# Sch_energia_luces.net
KiCad netlist of a schematic drawn in Altium Designer
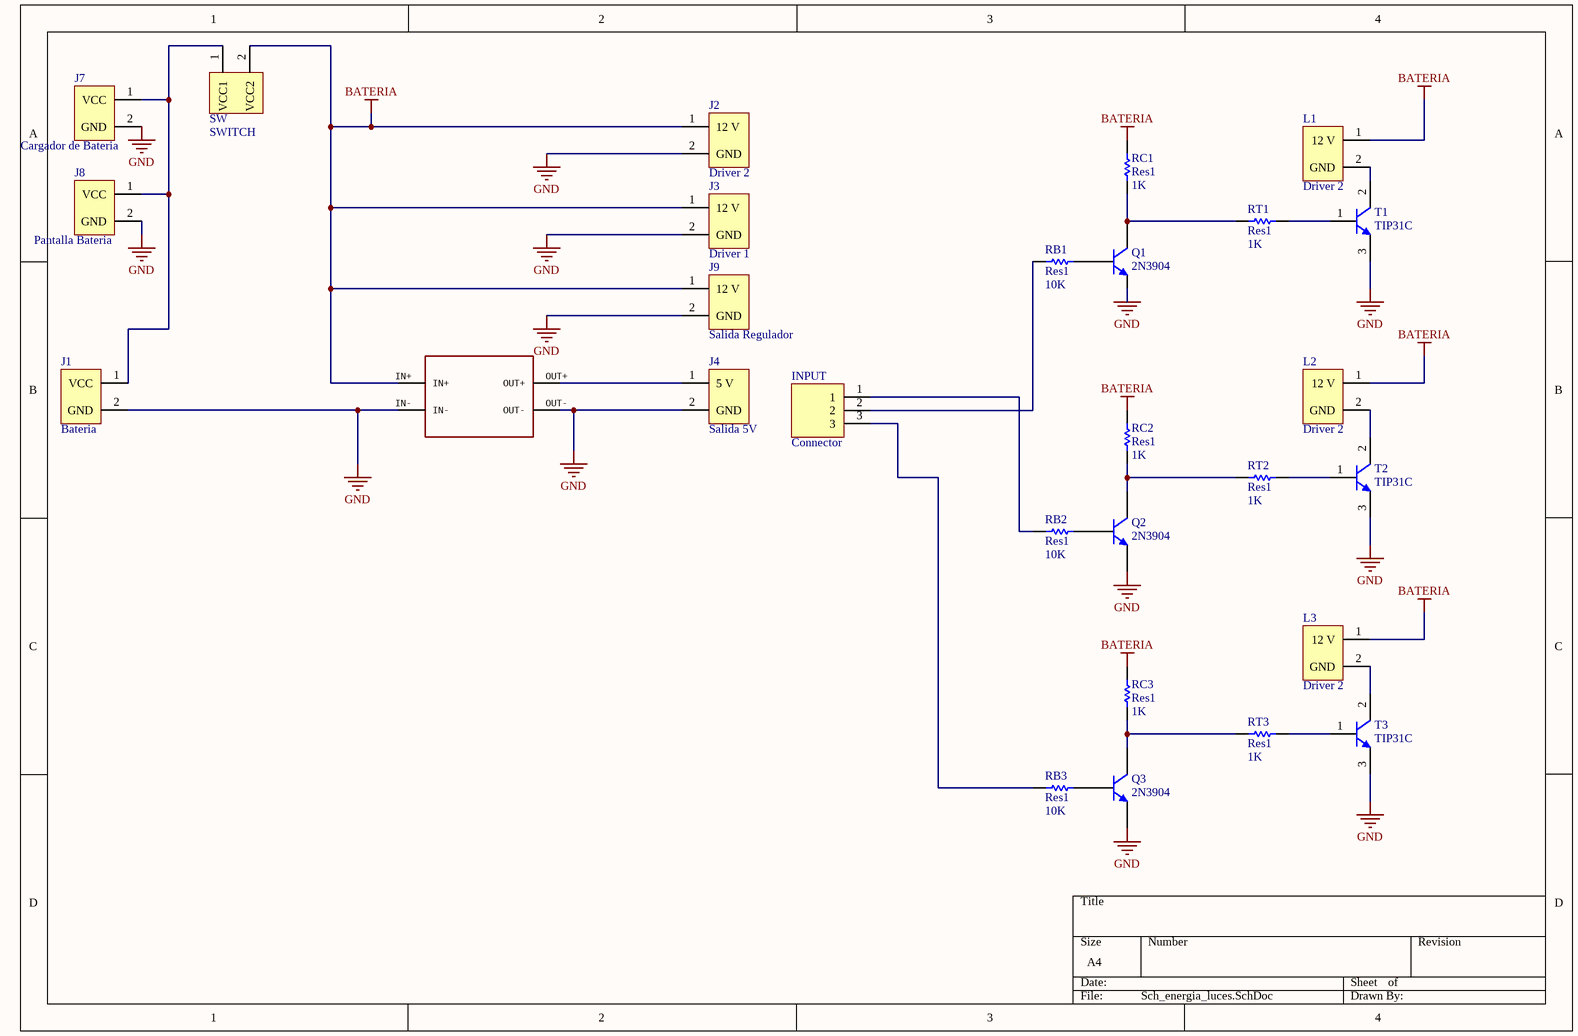
[diagram p0: Sch_energia_luces.SchDoc]

(export (version "E")
  (design (tool "Eeschema 10.0.6"))
  (components
    (comp (ref "INPUT")
      (value "Connector")
      (footprint "1x3x2.54 Pin Header TH V")
      (libsource (lib "CARO") (part "Header 1x3"))
    )
    (comp (ref "J1") (value "Bateria") (footprint "CONN2") (libsource (lib "Schlib1") (part "Bornera")))
    (comp (ref "J2") (value "Driver 2") (footprint "CONN2") (libsource (lib "") (part "Bornera_1")))
    (comp (ref "J3") (value "Driver 1") (footprint "CONN2") (libsource (lib "") (part "Bornera_1")))
    (comp (ref "J4") (value "Salida 5V") (footprint "CONN2") (libsource (lib "") (part "Bornera_2")))
    (comp (ref "J7")
      (value "Cargador de Bateria")
      (footprint "CONN2")
      (libsource (lib "Schlib1") (part "Bornera"))
    )
    (comp (ref "J8")
      (value "Pantalla Bateria")
      (footprint "CONN2")
      (libsource (lib "Schlib1") (part "Bornera"))
    )
    (comp (ref "J9") (value "Salida Regulador") (footprint "CONN2") (libsource (lib "") (part "Bornera_1")))
    (comp (ref "L1") (value "Driver 2") (footprint "CONN2") (libsource (lib "Schlib1") (part "Bornera")))
    (comp (ref "L2") (value "Driver 2") (footprint "CONN2") (libsource (lib "Schlib1") (part "Bornera")))
    (comp (ref "L3") (value "Driver 2") (footprint "CONN2") (libsource (lib "Schlib1") (part "Bornera")))
    (comp (ref "Q1")
      (value "2N3904")
      (footprint "TO-92A")
      (description "NPN General Purpose Amplifier")
      (fields (field (name "PUBLISHER") "Altium Limited"))
      (libsource (lib "Miscellaneous Devices") (part "2N3904"))
    )
    (comp (ref "Q2")
      (value "2N3904")
      (footprint "TO-92A")
      (description "NPN General Purpose Amplifier")
      (fields (field (name "PUBLISHER") "Altium Limited"))
      (libsource (lib "Miscellaneous Devices") (part "2N3904"))
    )
    (comp (ref "Q3")
      (value "2N3904")
      (footprint "TO-92A")
      (description "NPN General Purpose Amplifier")
      (fields (field (name "PUBLISHER") "Altium Limited"))
      (libsource (lib "Miscellaneous Devices") (part "2N3904"))
    )
    (comp (ref "RB1")
      (value "Res1")
      (footprint "AXIAL-0.3")
      (description "Resistor")
      (fields (field (name "ALTIUM_VALUE") "10K") (field (name "PUBLISHER") "Altium Limited"))
      (libsource (lib "Miscellaneous Devices") (part "Res1"))
    )
    (comp (ref "RB2")
      (value "Res1")
      (footprint "AXIAL-0.3")
      (description "Resistor")
      (fields (field (name "ALTIUM_VALUE") "10K") (field (name "PUBLISHER") "Altium Limited"))
      (libsource (lib "Miscellaneous Devices") (part "Res1"))
    )
    (comp (ref "RB3")
      (value "Res1")
      (footprint "AXIAL-0.3")
      (description "Resistor")
      (fields (field (name "ALTIUM_VALUE") "10K") (field (name "PUBLISHER") "Altium Limited"))
      (libsource (lib "Miscellaneous Devices") (part "Res1"))
    )
    (comp (ref "RC1")
      (value "Res1")
      (footprint "AXIAL-0.3")
      (description "Resistor")
      (fields (field (name "ALTIUM_VALUE") "1K") (field (name "PUBLISHER") "Altium Limited"))
      (libsource (lib "Miscellaneous Devices") (part "Res1"))
    )
    (comp (ref "RC2")
      (value "Res1")
      (footprint "AXIAL-0.3")
      (description "Resistor")
      (fields (field (name "ALTIUM_VALUE") "1K") (field (name "PUBLISHER") "Altium Limited"))
      (libsource (lib "Miscellaneous Devices") (part "Res1"))
    )
    (comp (ref "RC3")
      (value "Res1")
      (footprint "AXIAL-0.3")
      (description "Resistor")
      (fields (field (name "ALTIUM_VALUE") "1K") (field (name "PUBLISHER") "Altium Limited"))
      (libsource (lib "Miscellaneous Devices") (part "Res1"))
    )
    (comp (ref "REG1")
      (value "Voltage regulator IN: 7-35V OUT: ADJ")
      (footprint "CP8-ADJ")
      (fields (field (name "LIBRARYNAME") "userlib"))
      (libsource (lib "Integrated_Library1") (part "CP8-ADJ"))
    )
    (comp (ref "RT1")
      (value "Res1")
      (footprint "AXIAL-0.3")
      (description "Resistor")
      (fields (field (name "ALTIUM_VALUE") "1K") (field (name "PUBLISHER") "Altium Limited"))
      (libsource (lib "Miscellaneous Devices") (part "Res1"))
    )
    (comp (ref "RT2")
      (value "Res1")
      (footprint "AXIAL-0.3")
      (description "Resistor")
      (fields (field (name "ALTIUM_VALUE") "1K") (field (name "PUBLISHER") "Altium Limited"))
      (libsource (lib "Miscellaneous Devices") (part "Res1"))
    )
    (comp (ref "RT3")
      (value "Res1")
      (footprint "AXIAL-0.3")
      (description "Resistor")
      (fields (field (name "ALTIUM_VALUE") "1K") (field (name "PUBLISHER") "Altium Limited"))
      (libsource (lib "Miscellaneous Devices") (part "Res1"))
    )
    (comp (ref "SW") (value "SWITCH") (footprint "CONN2") (libsource (lib "") (part "Bornera_3")))
    (comp (ref "T1")
      (value "TIP31C")
      (footprint "ONSC-TO-220-3-221A-09")
      (description "Complementary Silicon Plastic Power Transistor, 3-Pin TO-220, Tube")
      (fields (field (name "MANUFACTURER") "On Semiconductor"))
      (libsource (lib "Altium Content Vault") (part "ONSC-NPN-B1C2E3-3_C"))
    )
    (comp (ref "T2")
      (value "TIP31C")
      (footprint "ONSC-TO-220-3-221A-09")
      (description "Complementary Silicon Plastic Power Transistor, 3-Pin TO-220, Tube")
      (fields (field (name "MANUFACTURER") "On Semiconductor"))
      (libsource (lib "Altium Content Vault") (part "ONSC-NPN-B1C2E3-3_C"))
    )
    (comp (ref "T3")
      (value "TIP31C")
      (footprint "ONSC-TO-220-3-221A-09")
      (description "Complementary Silicon Plastic Power Transistor, 3-Pin TO-220, Tube")
      (fields (field (name "MANUFACTURER") "On Semiconductor"))
      (libsource (lib "Altium Content Vault") (part "ONSC-NPN-B1C2E3-3_C"))
    )
  )
  (nets
    (net (code "1") (name "BATERIA") (class "Default")
      (node (ref "J2") (pin "1") (pinfunction "12_V_1") (pintype "passive"))
      (node (ref "J3") (pin "1") (pinfunction "12_V_1") (pintype "passive"))
      (node (ref "J9") (pin "1") (pinfunction "12_V_1") (pintype "passive"))
      (node (ref "L1") (pin "1") (pinfunction "VCC_1") (pintype "passive"))
      (node (ref "L2") (pin "1") (pinfunction "VCC_1") (pintype "passive"))
      (node (ref "L3") (pin "1") (pinfunction "VCC_1") (pintype "passive"))
      (node (ref "RC1") (pin "2") (pinfunction "2_2") (pintype "passive"))
      (node (ref "RC2") (pin "2") (pinfunction "2_2") (pintype "passive"))
      (node (ref "RC3") (pin "2") (pinfunction "2_2") (pintype "passive"))
      (node (ref "REG1") (pin "IN+") (pinfunction "IN+_IN+") (pintype "passive"))
      (node (ref "SW") (pin "2") (pinfunction "VCC2_2") (pintype "passive"))
    )
    (net (code "2") (name "GND") (class "Default")
      (node (ref "J1") (pin "2") (pinfunction "GND_2") (pintype "passive"))
      (node (ref "J2") (pin "2") (pinfunction "GND_2") (pintype "passive"))
      (node (ref "J3") (pin "2") (pinfunction "GND_2") (pintype "passive"))
      (node (ref "J4") (pin "2") (pinfunction "GND_2") (pintype "passive"))
      (node (ref "J7") (pin "2") (pinfunction "GND_2") (pintype "passive"))
      (node (ref "J8") (pin "2") (pinfunction "GND_2") (pintype "passive"))
      (node (ref "J9") (pin "2") (pinfunction "GND_2") (pintype "passive"))
      (node (ref "Q1") (pin "1") (pinfunction "E_1") (pintype "passive"))
      (node (ref "Q2") (pin "1") (pinfunction "E_1") (pintype "passive"))
      (node (ref "Q3") (pin "1") (pinfunction "E_1") (pintype "passive"))
      (node (ref "REG1") (pin "IN-") (pinfunction "IN-_IN-") (pintype "passive"))
      (node (ref "REG1") (pin "OUT-") (pinfunction "OUT-_OUT-") (pintype "passive"))
      (node (ref "T1") (pin "3") (pinfunction "E_3") (pintype "passive"))
      (node (ref "T2") (pin "3") (pinfunction "E_3") (pintype "passive"))
      (node (ref "T3") (pin "3") (pinfunction "E_3") (pintype "passive"))
    )
    (net (code "3") (name "Net-(INPUT-Pad1)") (class "Default")
      (node (ref "INPUT") (pin "1") (pinfunction "1_1") (pintype "passive"))
      (node (ref "RB2") (pin "1") (pinfunction "1_1") (pintype "passive"))
    )
    (net (code "4") (name "Net-(INPUT-Pad2)") (class "Default")
      (node (ref "INPUT") (pin "2") (pinfunction "2_2") (pintype "passive"))
      (node (ref "RB1") (pin "1") (pinfunction "1_1") (pintype "passive"))
    )
    (net (code "5") (name "Net-(INPUT-Pad3)") (class "Default")
      (node (ref "INPUT") (pin "3") (pinfunction "3_3") (pintype "passive"))
      (node (ref "RB3") (pin "1") (pinfunction "1_1") (pintype "passive"))
    )
    (net (code "6") (name "Net-(J1-VCC)") (class "Default")
      (node (ref "J1") (pin "1") (pinfunction "VCC_1") (pintype "passive"))
      (node (ref "J7") (pin "1") (pinfunction "VCC_1") (pintype "passive"))
      (node (ref "J8") (pin "1") (pinfunction "VCC_1") (pintype "passive"))
      (node (ref "SW") (pin "1") (pinfunction "VCC1_1") (pintype "passive"))
    )
    (net (code "7") (name "Net-(J4-5_V)") (class "Default")
      (node (ref "J4") (pin "1") (pinfunction "5_V_1") (pintype "passive"))
      (node (ref "REG1") (pin "OUT+") (pinfunction "OUT+_OUT+") (pintype "passive"))
    )
    (net (code "8") (name "Net-(L1-GND)") (class "Default")
      (node (ref "L1") (pin "2") (pinfunction "GND_2") (pintype "passive"))
      (node (ref "T1") (pin "2") (pinfunction "C_2") (pintype "passive"))
    )
    (net (code "9") (name "Net-(L2-GND)") (class "Default")
      (node (ref "L2") (pin "2") (pinfunction "GND_2") (pintype "passive"))
      (node (ref "T2") (pin "2") (pinfunction "C_2") (pintype "passive"))
    )
    (net (code "10") (name "Net-(L3-GND)") (class "Default")
      (node (ref "L3") (pin "2") (pinfunction "GND_2") (pintype "passive"))
      (node (ref "T3") (pin "2") (pinfunction "C_2") (pintype "passive"))
    )
    (net (code "11") (name "Net-(Q1-B)") (class "Default")
      (node (ref "Q1") (pin "2") (pinfunction "B_2") (pintype "passive"))
      (node (ref "RB1") (pin "2") (pinfunction "2_2") (pintype "passive"))
    )
    (net (code "12") (name "Net-(Q1-C)") (class "Default")
      (node (ref "Q1") (pin "3") (pinfunction "C_3") (pintype "passive"))
      (node (ref "RC1") (pin "1") (pinfunction "1_1") (pintype "passive"))
      (node (ref "RT1") (pin "1") (pinfunction "1_1") (pintype "passive"))
    )
    (net (code "13") (name "Net-(Q2-B)") (class "Default")
      (node (ref "Q2") (pin "2") (pinfunction "B_2") (pintype "passive"))
      (node (ref "RB2") (pin "2") (pinfunction "2_2") (pintype "passive"))
    )
    (net (code "14") (name "Net-(Q2-C)") (class "Default")
      (node (ref "Q2") (pin "3") (pinfunction "C_3") (pintype "passive"))
      (node (ref "RC2") (pin "1") (pinfunction "1_1") (pintype "passive"))
      (node (ref "RT2") (pin "1") (pinfunction "1_1") (pintype "passive"))
    )
    (net (code "15") (name "Net-(Q3-B)") (class "Default")
      (node (ref "Q3") (pin "2") (pinfunction "B_2") (pintype "passive"))
      (node (ref "RB3") (pin "2") (pinfunction "2_2") (pintype "passive"))
    )
    (net (code "16") (name "Net-(Q3-C)") (class "Default")
      (node (ref "Q3") (pin "3") (pinfunction "C_3") (pintype "passive"))
      (node (ref "RC3") (pin "1") (pinfunction "1_1") (pintype "passive"))
      (node (ref "RT3") (pin "1") (pinfunction "1_1") (pintype "passive"))
    )
    (net (code "17") (name "Net-(T1-B)") (class "Default")
      (node (ref "RT1") (pin "2") (pinfunction "2_2") (pintype "passive"))
      (node (ref "T1") (pin "1") (pinfunction "B_1") (pintype "passive"))
    )
    (net (code "18") (name "Net-(T2-B)") (class "Default")
      (node (ref "RT2") (pin "2") (pinfunction "2_2") (pintype "passive"))
      (node (ref "T2") (pin "1") (pinfunction "B_1") (pintype "passive"))
    )
    (net (code "19") (name "Net-(T3-B)") (class "Default")
      (node (ref "RT3") (pin "2") (pinfunction "2_2") (pintype "passive"))
      (node (ref "T3") (pin "1") (pinfunction "B_1") (pintype "passive"))
    )
  )
)
